# CH32F207VCT6-R1.net
KiCad netlist of a schematic drawn in Altium Designer
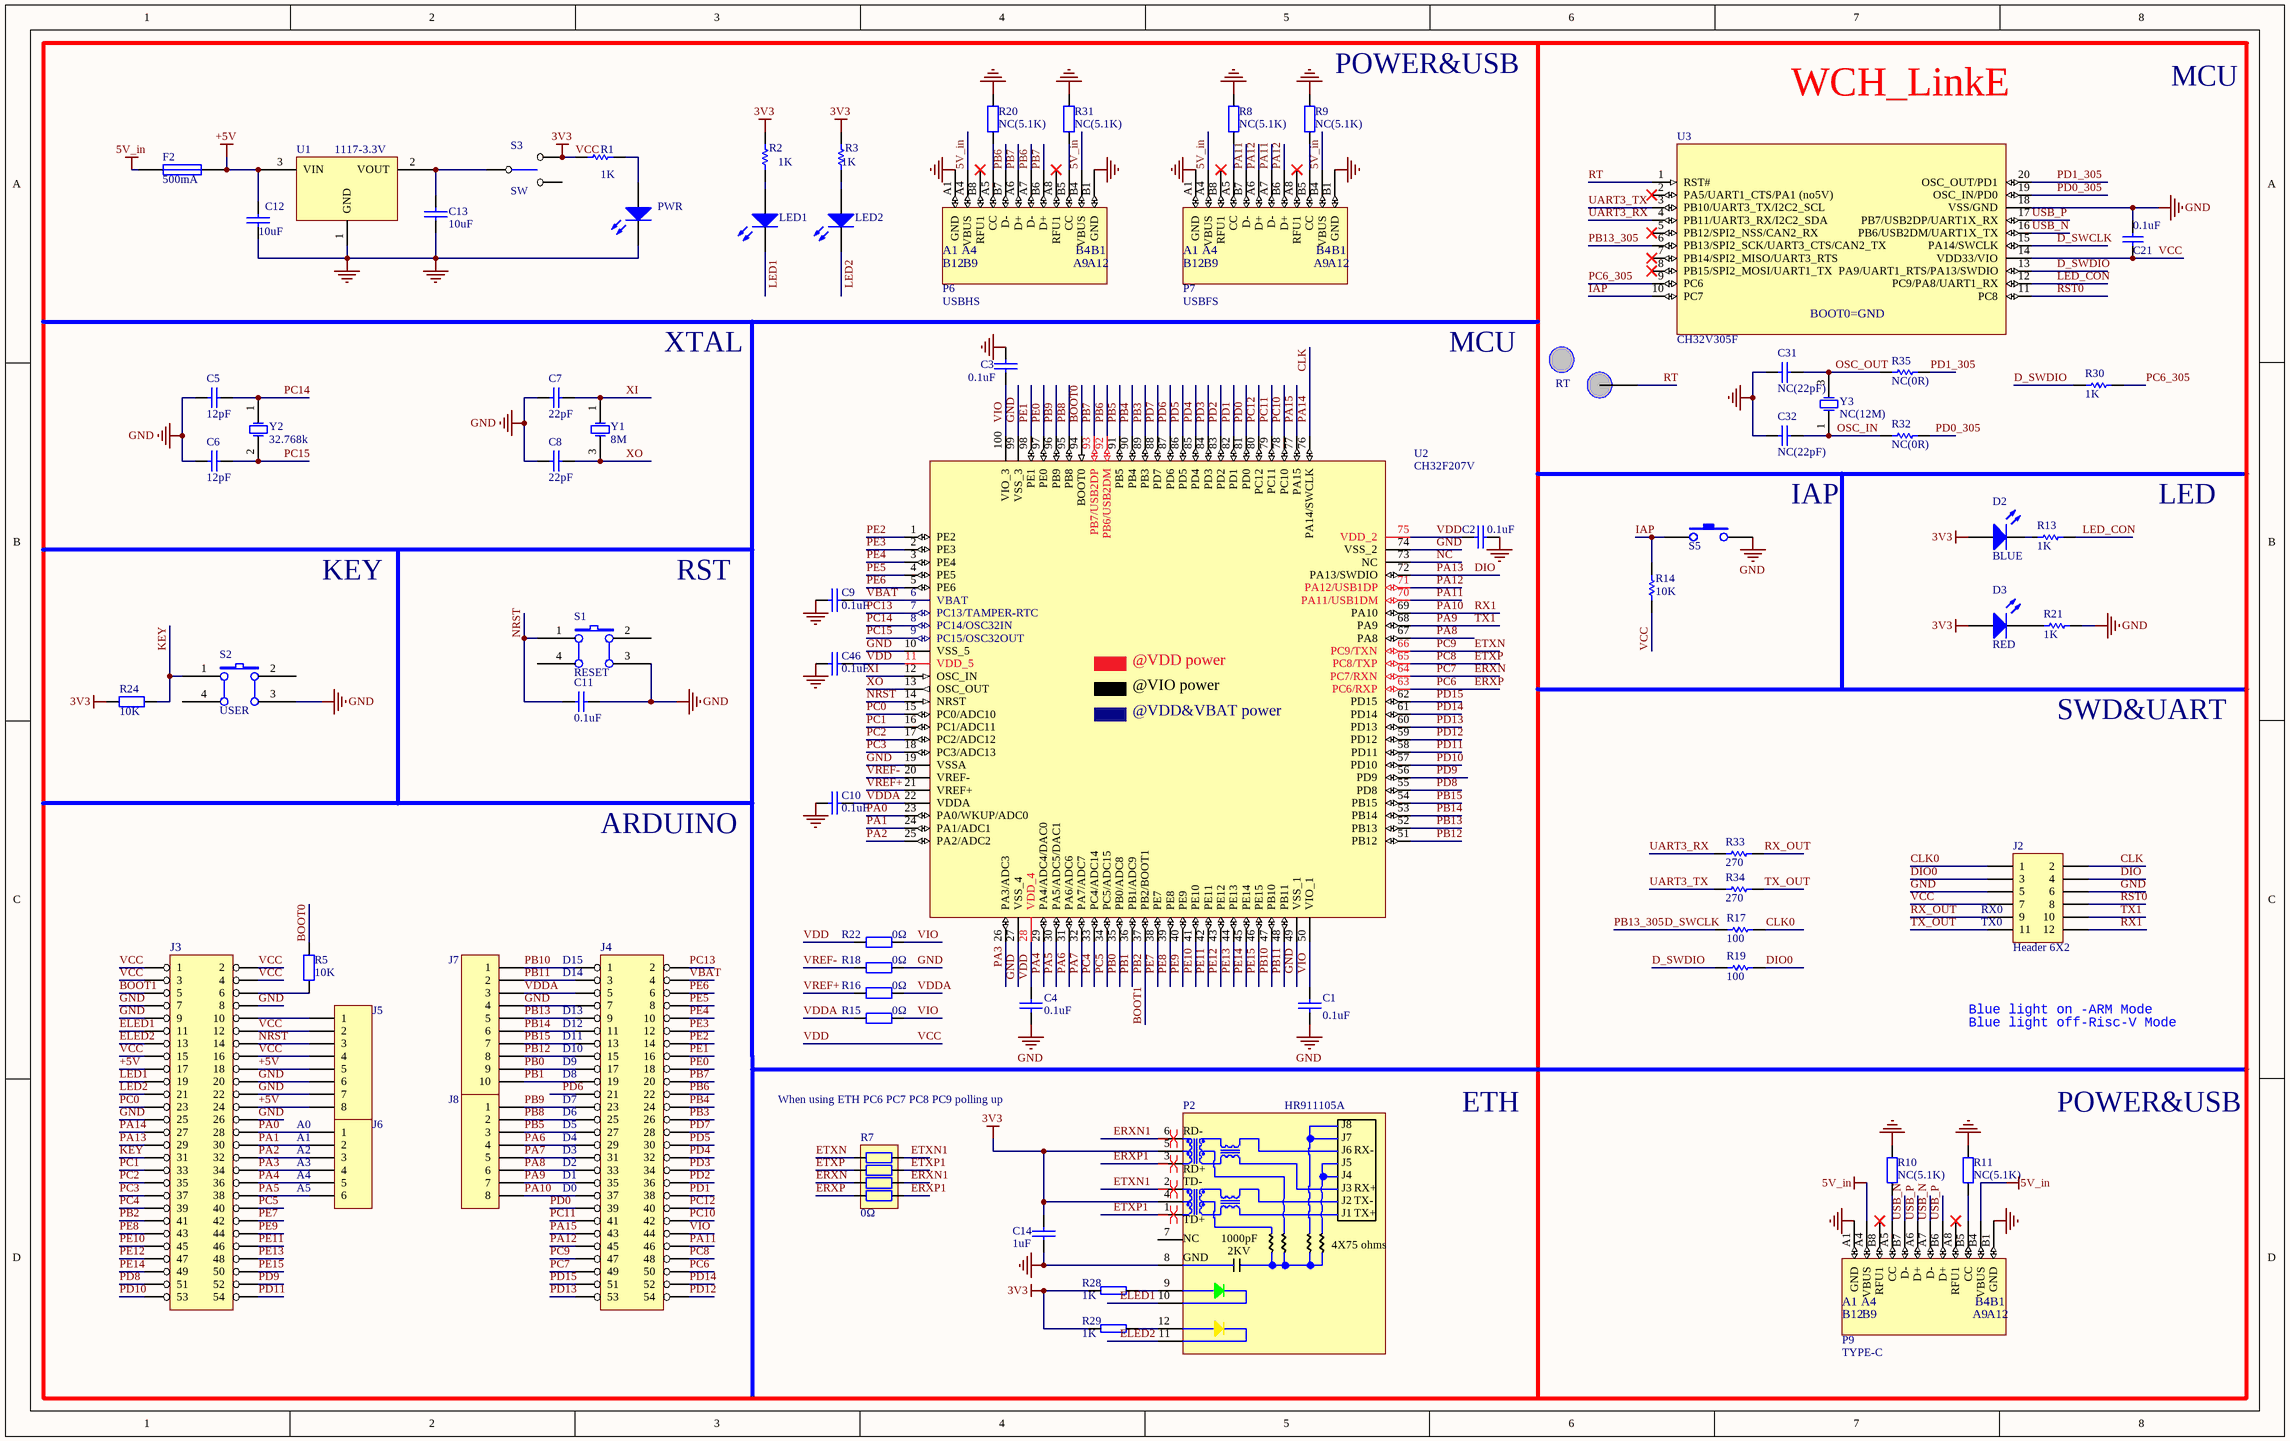
[diagram p0: CH32F207VCT6-R1.SchDoc]

(export (version "E")
  (design (tool "Eeschema 10.0.6"))
  (components
    (comp (ref "C1")
      (value "0.1uF")
      (footprint "0603_C")
      (description "Capacitor")
      (libsource (lib "*") (part "CAP"))
    )
    (comp (ref "C2")
      (value "0.1uF")
      (footprint "0603_C")
      (description "Capacitor")
      (libsource (lib "*") (part "CAP"))
    )
    (comp (ref "C3")
      (value "0.1uF")
      (footprint "0603_C")
      (description "Capacitor")
      (libsource (lib "*") (part "CAP"))
    )
    (comp (ref "C4")
      (value "0.1uF")
      (footprint "0603_C")
      (description "Capacitor")
      (libsource (lib "*") (part "CAP"))
    )
    (comp (ref "C5")
      (value "12pF")
      (footprint "0603_C")
      (description "Capacitor")
      (libsource (lib "Miscellaneous Devices") (part "Cap"))
    )
    (comp (ref "C6")
      (value "12pF")
      (footprint "0603_C")
      (description "Capacitor")
      (libsource (lib "Miscellaneous Devices") (part "Cap"))
    )
    (comp (ref "C7")
      (value "22pF")
      (footprint "0603_C")
      (description "Capacitor")
      (libsource (lib "Miscellaneous Devices") (part "Cap"))
    )
    (comp (ref "C8")
      (value "22pF")
      (footprint "0603_C")
      (description "Capacitor")
      (libsource (lib "Miscellaneous Devices") (part "Cap"))
    )
    (comp (ref "C9")
      (value "0.1uF")
      (footprint "0603_C")
      (description "Capacitor")
      (libsource (lib "*") (part "CAP"))
    )
    (comp (ref "C10")
      (value "0.1uF")
      (footprint "0603_C")
      (description "Capacitor")
      (libsource (lib "*") (part "CAP"))
    )
    (comp (ref "C11")
      (value "0.1uF")
      (footprint "0603_C")
      (description "Capacitor")
      (libsource (lib "Miscellaneous Devices") (part "Cap"))
    )
    (comp (ref "C12")
      (value "10uF")
      (footprint "3216_C")
      (description "Capacitor")
      (libsource (lib "*") (part "CAP"))
    )
    (comp (ref "C13")
      (value "10uF")
      (footprint "3216_C")
      (description "Capacitor")
      (libsource (lib "*") (part "CAP"))
    )
    (comp (ref "C14")
      (value "1uF")
      (footprint "0603_C")
      (description "Capacitor")
      (libsource (lib "*") (part "CAP"))
    )
    (comp (ref "C21")
      (value "0.1uF")
      (footprint "0603_C")
      (description "Capacitor")
      (libsource (lib "Miscellaneous Devices") (part "Cap"))
    )
    (comp (ref "C31")
      (value "NC(22pF)")
      (footprint "0603_C")
      (description "Capacitor")
      (libsource (lib "*") (part "Cap"))
    )
    (comp (ref "C32")
      (value "NC(22pF)")
      (footprint "0603_C")
      (description "Capacitor")
      (libsource (lib "*") (part "Cap"))
    )
    (comp (ref "C46")
      (value "0.1uF")
      (footprint "0603_C")
      (description "Capacitor")
      (libsource (lib "*") (part "CAP"))
    )
    (comp (ref "D2")
      (value "BLUE")
      (footprint "0603+")
      (description "Typical RED, GREEN, YELLOW, AMBER GaAs LED")
      (libsource (lib "MYLIB") (part "D0603"))
    )
    (comp (ref "D3")
      (value "RED")
      (footprint "0603+")
      (description "Typical RED, GREEN, YELLOW, AMBER GaAs LED")
      (libsource (lib "MYLIB") (part "D0603"))
    )
    (comp (ref "F2")
      (value "500mA")
      (footprint "0805")
      (description "Fuse")
      (libsource (lib "*") (part "FUSE1"))
    )
    (comp (ref "J2")
      (value "Header 6X2")
      (footprint "IDC12-2.54mm")
      (description "Header, 6-Pin, Dual row")
      (libsource (lib "Miscellaneous Connectors") (part "Header 6X2"))
    )
    (comp (ref "J3")
      (value "HEADER 27x2")
      (footprint "MYPCB:IDC54-2.54MM")
      (description "Header, 27-Pin, Dual row")
      (libsource (lib "wch_sch_others") (part "HEADER 27x2"))
    )
    (comp (ref "J4")
      (value "HEADER 27x2")
      (footprint "MYPCB:IDC54-2.54MM")
      (description "Header, 27-Pin, Dual row")
      (libsource (lib "wch_sch_others") (part "HEADER 27x2"))
    )
    (comp (ref "J5")
      (value "Header 8")
      (footprint "SIP8-2.54mm")
      (description "Header, 8-Pin")
      (libsource (lib "Miscellaneous Connectors") (part "Header 8"))
    )
    (comp (ref "J6")
      (value "Header 6")
      (footprint "SIP6-2.54MM")
      (description "Header, 6-Pin")
      (libsource (lib "Miscellaneous Connectors") (part "Header 6"))
    )
    (comp (ref "J7")
      (value "Header 10")
      (footprint "SIP10-2.54mm")
      (description "Header, 10-Pin")
      (libsource (lib "Miscellaneous Connectors") (part "Header 10"))
    )
    (comp (ref "J8")
      (value "Header 8")
      (footprint "SIP8-2.54mm")
      (description "Header, 8-Pin")
      (libsource (lib "") (part "Header 8_1"))
    )
    (comp (ref "LED1")
      (value "LED1   blue")
      (footprint "0603+")
      (description "Typical INFRARED GaAs LED")
      (libsource (lib "Miscellaneous Devices") (part "LED0"))
    )
    (comp (ref "LED2")
      (value "LED2  blue")
      (footprint "0603+")
      (description "Typical INFRARED GaAs LED")
      (libsource (lib "Miscellaneous Devices") (part "LED0"))
    )
    (comp (ref "P2") (value "HR911105A") (footprint "HR911105A") (libsource (lib "*") (part "HR911105A")))
    (comp (ref "P6")
      (value "USBHS")
      (footprint "TYPE-C-Receptacle-2.0")
      (libsource (lib "*") (part "TYPE-C1"))
    )
    (comp (ref "P7")
      (value "USBFS")
      (footprint "TYPE-C-Receptacle-2.0")
      (libsource (lib "*") (part "TYPE-C1"))
    )
    (comp (ref "P9")
      (value "TYPE-C")
      (footprint "TYPE-C-Receptacle-2.0")
      (libsource (lib "*") (part "TYPE-C1"))
    )
    (comp (ref "PWR")
      (value "POWER  red")
      (footprint "0603+")
      (description "Typical INFRARED GaAs LED")
      (libsource (lib "Miscellaneous Devices") (part "LED0"))
    )
    (comp (ref "R1")
      (value "1K")
      (footprint "0603")
      (description "Semiconductor Resistor")
      (libsource (lib "Miscellaneous Devices") (part "Res Semi"))
    )
    (comp (ref "R2")
      (value "1K")
      (footprint "0603")
      (description "Semiconductor Resistor")
      (libsource (lib "Miscellaneous Devices") (part "Res Semi"))
    )
    (comp (ref "R3")
      (value "1K")
      (footprint "0603")
      (description "Semiconductor Resistor")
      (libsource (lib "Miscellaneous Devices") (part "Res Semi"))
    )
    (comp (ref "R5")
      (value "10K")
      (footprint "0603")
      (description "Resistor")
      (libsource (lib "") (part "Res2_1"))
    )
    (comp (ref "R7")
      (value "0Ω")
      (footprint "RCA-8P4R-0603")
      (description "贴片网络排阻")
      (libsource (lib "wch_sch_others") (part "R-8P4R"))
    )
    (comp (ref "R8")
      (value "NC(5.1K)")
      (footprint "0603")
      (description "Resistor")
      (libsource (lib "") (part "Res2_2"))
    )
    (comp (ref "R9")
      (value "NC(5.1K)")
      (footprint "0603")
      (description "Resistor")
      (libsource (lib "") (part "Res2_2"))
    )
    (comp (ref "R10")
      (value "NC(5.1K)")
      (footprint "0603")
      (description "Resistor")
      (libsource (lib "") (part "Res2_1"))
    )
    (comp (ref "R11")
      (value "NC(5.1K)")
      (footprint "0603")
      (description "Resistor")
      (libsource (lib "") (part "Res2_1"))
    )
    (comp (ref "R13")
      (value "1K")
      (footprint "0603")
      (description "Resistor")
      (libsource (lib "MYLIB") (part "0603-1"))
    )
    (comp (ref "R14")
      (value "10K")
      (footprint "0603")
      (description "Resistor")
      (libsource (lib "MYLIB") (part "0603-1"))
    )
    (comp (ref "R15")
      (value "0Ω")
      (footprint "0603")
      (description "Resistor")
      (libsource (lib "Miscellaneous Devices") (part "Res2"))
    )
    (comp (ref "R16")
      (value "0Ω")
      (footprint "0603")
      (description "Resistor")
      (libsource (lib "Miscellaneous Devices") (part "Res2"))
    )
    (comp (ref "R17")
      (value "100")
      (footprint "0603")
      (description "Resistor")
      (libsource (lib "MYLIB") (part "0603-1"))
    )
    (comp (ref "R18")
      (value "0Ω")
      (footprint "0603")
      (description "Resistor")
      (libsource (lib "Miscellaneous Devices") (part "Res2"))
    )
    (comp (ref "R19")
      (value "100")
      (footprint "0603")
      (description "Resistor")
      (libsource (lib "MYLIB") (part "0603-1"))
    )
    (comp (ref "R20")
      (value "NC(5.1K)")
      (footprint "0603")
      (description "Resistor")
      (libsource (lib "") (part "Res2_2"))
    )
    (comp (ref "R21")
      (value "1K")
      (footprint "0603")
      (description "Resistor")
      (libsource (lib "MYLIB") (part "0603-1"))
    )
    (comp (ref "R22")
      (value "0Ω")
      (footprint "0603")
      (description "Resistor")
      (libsource (lib "Miscellaneous Devices") (part "Res2"))
    )
    (comp (ref "R24")
      (value "10K")
      (footprint "0603")
      (description "Resistor")
      (libsource (lib "Miscellaneous Devices") (part "Res2"))
    )
    (comp (ref "R28") (value "1K") (footprint "0603") (libsource (lib "wch_sch_others") (part "RES")))
    (comp (ref "R29") (value "1K") (footprint "0603") (libsource (lib "wch_sch_others") (part "RES")))
    (comp (ref "R30")
      (value "1K")
      (footprint "0603")
      (description "Resistor")
      (libsource (lib "MYLIB") (part "0603-1"))
    )
    (comp (ref "R31")
      (value "NC(5.1K)")
      (footprint "0603")
      (description "Resistor")
      (libsource (lib "") (part "Res2_2"))
    )
    (comp (ref "R32")
      (value "NC(0R)")
      (footprint "0603")
      (description "Resistor")
      (libsource (lib "MYLIB") (part "0603-1"))
    )
    (comp (ref "R33")
      (value "270")
      (footprint "0603")
      (description "Resistor")
      (libsource (lib "MYLIB") (part "0603-1"))
    )
    (comp (ref "R34")
      (value "270")
      (footprint "0603")
      (description "Resistor")
      (libsource (lib "MYLIB") (part "0603-1"))
    )
    (comp (ref "R35")
      (value "NC(0R)")
      (footprint "0603")
      (description "Resistor")
      (libsource (lib "MYLIB") (part "0603-1"))
    )
    (comp (ref "RT")
      (value "Testpoint")
      (footprint "TESTPOINT1")
      (description "测试点")
      (libsource (lib "wch_sch_others") (part "Testpoint"))
    )
    (comp (ref "S1")
      (value "RESET")
      (footprint "KEYX")
      (description "SE PUSHBUTTON")
      (libsource (lib "Documents") (part "SW PUSHBUTTON"))
    )
    (comp (ref "S2")
      (value "USER")
      (footprint "KEYX")
      (description "SE PUSHBUTTON")
      (libsource (lib "Documents") (part "SW PUSHBUTTON"))
    )
    (comp (ref "S3") (value "SW") (footprint "SW1") (libsource (lib "MYSCH") (part "SW")))
    (comp (ref "S5") (value "KEY") (footprint "贴片按键") (libsource (lib "*") (part "KEY")))
    (comp (ref "U1")
      (value "1117-3.3V")
      (footprint "SOT-223")
      (libsource (lib "wch_sch_others") (part "1117-3.3V"))
    )
    (comp (ref "U2")
      (value "CH32F207V")
      (footprint "LQFP100")
      (description "ARM M3 HD-MCU, 144MHz, USB_480M, USB OTG, 1000M Ethernet MAC, 2*CAN")
      (libsource (lib "CHXXX") (part "CH32F207V"))
    )
    (comp (ref "U3")
      (value "CH32V305F")
      (footprint "TSSOP20")
      (description "RISC-V FPU HD-MCU, 144MHz, USB_480M, CAN, UART*2, SPI")
      (libsource (lib "CHXXX") (part "CH32V305F"))
    )
    (comp (ref "Y1")
      (value "8M")
      (footprint "XT3225")
      (description "Crystal Oscillator")
      (libsource (lib "Miscellaneous Devices") (part "XTAL"))
    )
    (comp (ref "Y2")
      (value "32.768k")
      (footprint "FC-135")
      (description "Crystal Oscillator")
      (libsource (lib "") (part "XTAL_1"))
    )
    (comp (ref "Y3")
      (value "NC(12M)")
      (footprint "XT3225")
      (description "Crystal Oscillator")
      (libsource (lib "*") (part "XTAL"))
    )
  )
  (nets
    (net (code "1") (name "+5V") (class "Default")
      (node (ref "C12") (pin "1") (pinfunction "1_1") (pintype "passive"))
      (node (ref "F2") (pin "2") (pinfunction "2_2") (pintype "passive"))
      (node (ref "J3") (pin "17") (pinfunction "17_17") (pintype "passive"))
      (node (ref "J3") (pin "18") (pinfunction "18_18") (pintype "passive"))
      (node (ref "J3") (pin "24") (pinfunction "24_24") (pintype "passive"))
      (node (ref "J5") (pin "5") (pinfunction "5_5") (pintype "passive"))
      (node (ref "J5") (pin "8") (pinfunction "8_8") (pintype "passive"))
      (node (ref "U1") (pin "3") (pinfunction "VIN_3") (pintype "passive"))
    )
    (net (code "2") (name "/BOOT0") (class "Default")
      (node (ref "R5") (pin "2") (pinfunction "2_2") (pintype "passive"))
      (node (ref "U2") (pin "94") (pinfunction "BOOT0_94") (pintype "input"))
    )
    (net (code "3") (name "/BOOT1") (class "Default")
      (node (ref "J3") (pin "41") (pinfunction "41_41") (pintype "passive"))
      (node (ref "J3") (pin "5") (pinfunction "5_5") (pintype "passive"))
      (node (ref "U2") (pin "37") (pinfunction "PB2/BOOT1_37") (pintype "bidirectional"))
    )
    (net (code "4") (name "/CLK") (class "Default")
      (node (ref "J2") (pin "2") (pinfunction "2_2") (pintype "passive"))
      (node (ref "J3") (pin "27") (pinfunction "27_27") (pintype "passive"))
      (node (ref "U2") (pin "76") (pinfunction "PA14/SWCLK_76") (pintype "bidirectional"))
    )
    (net (code "5") (name "/CLK0") (class "Default")
      (node (ref "J2") (pin "1") (pinfunction "1_1") (pintype "passive"))
      (node (ref "R17") (pin "1") (pinfunction "1_1") (pintype "passive"))
    )
    (net (code "6") (name "/DIO") (class "Default")
      (node (ref "J2") (pin "4") (pinfunction "4_4") (pintype "passive"))
      (node (ref "J3") (pin "29") (pinfunction "29_29") (pintype "passive"))
      (node (ref "U2") (pin "72") (pinfunction "PA13/SWDIO_72") (pintype "bidirectional"))
    )
    (net (code "7") (name "/DIO0") (class "Default")
      (node (ref "J2") (pin "3") (pinfunction "3_3") (pintype "passive"))
      (node (ref "R19") (pin "1") (pinfunction "1_1") (pintype "passive"))
    )
    (net (code "8") (name "/D_SWCLK") (class "Default")
      (node (ref "R17") (pin "2") (pinfunction "2_2") (pintype "passive"))
      (node (ref "U3") (pin "15") (pinfunction "PA14/SWCLK_15") (pintype "bidirectional"))
      (node (ref "U3") (pin "6") (pinfunction "PB13/SPI2_SCK/UART3_CTS/CAN2_TX_6") (pintype "bidirectional"))
    )
    (net (code "9") (name "/D_SWDIO") (class "Default")
      (node (ref "R19") (pin "2") (pinfunction "2_2") (pintype "passive"))
      (node (ref "R30") (pin "1") (pinfunction "1_1") (pintype "passive"))
      (node (ref "U3") (pin "13") (pinfunction "PA9/UART1_RTS/PA13/SWDIO_13") (pintype "bidirectional"))
    )
    (net (code "10") (name "/ELED1") (class "Default")
      (node (ref "J3") (pin "11") (pinfunction "11_11") (pintype "passive"))
      (node (ref "P2") (pin "10") (pintype "passive"))
    )
    (net (code "11") (name "/ELED2") (class "Default")
      (node (ref "J3") (pin "13") (pinfunction "13_13") (pintype "passive"))
      (node (ref "P2") (pin "11") (pintype "passive"))
    )
    (net (code "12") (name "/ERXN") (class "Default")
      (node (ref "J4") (pin "49") (pinfunction "49_49") (pintype "passive"))
      (node (ref "R7") (pin "3") (pinfunction "3_3") (pintype "passive"))
      (node (ref "U2") (pin "64") (pinfunction "PC7/RXN_64") (pintype "bidirectional"))
    )
    (net (code "13") (name "/ERXN1") (class "Default")
      (node (ref "P2") (pin "6") (pintype "passive"))
      (node (ref "R7") (pin "6") (pinfunction "6_6") (pintype "passive"))
    )
    (net (code "14") (name "/ERXP") (class "Default")
      (node (ref "J4") (pin "50") (pinfunction "50_50") (pintype "passive"))
      (node (ref "R7") (pin "4") (pinfunction "4_4") (pintype "passive"))
      (node (ref "U2") (pin "63") (pinfunction "PC6/RXP_63") (pintype "bidirectional"))
    )
    (net (code "15") (name "/ERXP1") (class "Default")
      (node (ref "P2") (pin "3") (pintype "passive"))
      (node (ref "R7") (pin "5") (pinfunction "5_5") (pintype "passive"))
    )
    (net (code "16") (name "/ETXN") (class "Default")
      (node (ref "J4") (pin "47") (pinfunction "47_47") (pintype "passive"))
      (node (ref "R7") (pin "1") (pinfunction "1_1") (pintype "passive"))
      (node (ref "U2") (pin "66") (pinfunction "PC9/TXN_66") (pintype "bidirectional"))
    )
    (net (code "17") (name "/ETXN1") (class "Default")
      (node (ref "P2") (pin "2") (pintype "passive"))
      (node (ref "R7") (pin "8") (pinfunction "8_8") (pintype "passive"))
    )
    (net (code "18") (name "/ETXP") (class "Default")
      (node (ref "J4") (pin "48") (pinfunction "48_48") (pintype "passive"))
      (node (ref "R7") (pin "2") (pinfunction "2_2") (pintype "passive"))
      (node (ref "U2") (pin "65") (pinfunction "PC8/TXP_65") (pintype "bidirectional"))
    )
    (net (code "19") (name "/ETXP1") (class "Default")
      (node (ref "P2") (pin "1") (pintype "passive"))
      (node (ref "R7") (pin "7") (pinfunction "7_7") (pintype "passive"))
    )
    (net (code "20") (name "/IAP") (class "Default")
      (node (ref "R14") (pin "1") (pinfunction "1_1") (pintype "passive"))
      (node (ref "S5") (pin "1") (pinfunction "1_1") (pintype "passive"))
      (node (ref "U3") (pin "10") (pinfunction "PC7_10") (pintype "bidirectional"))
    )
    (net (code "21") (name "/KEY") (class "Default")
      (node (ref "J3") (pin "31") (pinfunction "31_31") (pintype "passive"))
      (node (ref "R24") (pin "1") (pinfunction "1_1") (pintype "passive"))
      (node (ref "S2") (pin "1") (pinfunction "A0_1") (pintype "passive"))
    )
    (net (code "22") (name "/LED1") (class "Default")
      (node (ref "J3") (pin "19") (pinfunction "19_19") (pintype "passive"))
      (node (ref "LED1") (pin "2") (pinfunction "K_2") (pintype "passive"))
    )
    (net (code "23") (name "/LED2") (class "Default")
      (node (ref "J3") (pin "21") (pinfunction "21_21") (pintype "passive"))
      (node (ref "LED2") (pin "2") (pinfunction "K_2") (pintype "passive"))
    )
    (net (code "24") (name "/LED_CON") (class "Default")
      (node (ref "R13") (pin "1") (pinfunction "1_1") (pintype "passive"))
      (node (ref "U3") (pin "12") (pinfunction "PC9/PA8/UART1_RX_12") (pintype "bidirectional"))
    )
    (net (code "25") (name "/NC") (class "Default")
      (node (ref "U2") (pin "73") (pinfunction "NC_73") (pintype "tri_state"))
    )
    (net (code "26") (name "/NRST") (class "Default")
      (node (ref "C11") (pin "2") (pinfunction "2_2") (pintype "passive"))
      (node (ref "J3") (pin "14") (pinfunction "14_14") (pintype "passive"))
      (node (ref "J5") (pin "3") (pinfunction "3_3") (pintype "passive"))
      (node (ref "S1") (pin "1") (pinfunction "A0_1") (pintype "passive"))
      (node (ref "U2") (pin "14") (pinfunction "NRST_14") (pintype "input"))
    )
    (net (code "27") (name "/OSC_IN") (class "Default")
      (node (ref "C32") (pin "2") (pinfunction "2_2") (pintype "passive"))
      (node (ref "R32") (pin "2") (pinfunction "2_2") (pintype "passive"))
      (node (ref "Y3") (pin "1") (pinfunction "OSC1_1") (pintype "passive"))
    )
    (net (code "28") (name "/OSC_OUT") (class "Default")
      (node (ref "C31") (pin "2") (pinfunction "2_2") (pintype "passive"))
      (node (ref "R35") (pin "2") (pinfunction "2_2") (pintype "passive"))
      (node (ref "Y3") (pin "3") (pinfunction "OSC2_3") (pintype "passive"))
    )
    (net (code "29") (name "/PA0") (class "Default")
      (node (ref "J3") (pin "28") (pinfunction "28_28") (pintype "passive"))
      (node (ref "J6") (pin "1") (pinfunction "1_1") (pintype "passive"))
      (node (ref "U2") (pin "23") (pinfunction "PA0/WKUP/ADC0_23") (pintype "bidirectional"))
    )
    (net (code "30") (name "/PA1") (class "Default")
      (node (ref "J3") (pin "30") (pinfunction "30_30") (pintype "passive"))
      (node (ref "J6") (pin "2") (pinfunction "2_2") (pintype "passive"))
      (node (ref "U2") (pin "24") (pinfunction "PA1/ADC1_24") (pintype "bidirectional"))
    )
    (net (code "31") (name "/PA2") (class "Default")
      (node (ref "J3") (pin "32") (pinfunction "32_32") (pintype "passive"))
      (node (ref "J6") (pin "3") (pinfunction "3_3") (pintype "passive"))
      (node (ref "U2") (pin "25") (pinfunction "PA2/ADC2_25") (pintype "bidirectional"))
    )
    (net (code "32") (name "/PA3") (class "Default")
      (node (ref "J3") (pin "34") (pinfunction "34_34") (pintype "passive"))
      (node (ref "J6") (pin "4") (pinfunction "4_4") (pintype "passive"))
      (node (ref "U2") (pin "26") (pinfunction "PA3/ADC3_26") (pintype "bidirectional"))
    )
    (net (code "33") (name "/PA4") (class "Default")
      (node (ref "J3") (pin "36") (pinfunction "36_36") (pintype "passive"))
      (node (ref "J6") (pin "5") (pinfunction "5_5") (pintype "passive"))
      (node (ref "U2") (pin "29") (pinfunction "PA4/ADC4/DAC0_29") (pintype "bidirectional"))
    )
    (net (code "34") (name "/PA5") (class "Default")
      (node (ref "J3") (pin "38") (pinfunction "38_38") (pintype "passive"))
      (node (ref "J6") (pin "6") (pinfunction "6_6") (pintype "passive"))
      (node (ref "U2") (pin "30") (pinfunction "PA5/ADC5/DAC1_30") (pintype "bidirectional"))
    )
    (net (code "35") (name "/PA6") (class "Default")
      (node (ref "J4") (pin "29") (pinfunction "29_29") (pintype "passive"))
      (node (ref "J8") (pin "4") (pinfunction "4_4") (pintype "passive"))
      (node (ref "U2") (pin "31") (pinfunction "PA6/ADC6_31") (pintype "bidirectional"))
    )
    (net (code "36") (name "/PA7") (class "Default")
      (node (ref "J4") (pin "31") (pinfunction "31_31") (pintype "passive"))
      (node (ref "J8") (pin "5") (pinfunction "5_5") (pintype "passive"))
      (node (ref "U2") (pin "32") (pinfunction "PA7/ADC7_32") (pintype "bidirectional"))
    )
    (net (code "37") (name "/PA8") (class "Default")
      (node (ref "J4") (pin "33") (pinfunction "33_33") (pintype "passive"))
      (node (ref "J8") (pin "6") (pinfunction "6_6") (pintype "passive"))
      (node (ref "U2") (pin "67") (pinfunction "PA8_67") (pintype "bidirectional"))
    )
    (net (code "38") (name "/PA9") (class "Default")
      (node (ref "J2") (pin "10") (pinfunction "10_10") (pintype "passive"))
      (node (ref "J4") (pin "35") (pinfunction "35_35") (pintype "passive"))
      (node (ref "J8") (pin "7") (pinfunction "7_7") (pintype "passive"))
      (node (ref "U2") (pin "68") (pinfunction "PA9_68") (pintype "bidirectional"))
    )
    (net (code "39") (name "/PA10") (class "Default")
      (node (ref "J2") (pin "12") (pinfunction "12_12") (pintype "passive"))
      (node (ref "J4") (pin "37") (pinfunction "37_37") (pintype "passive"))
      (node (ref "J8") (pin "8") (pinfunction "8_8") (pintype "passive"))
      (node (ref "U2") (pin "69") (pinfunction "PA10_69") (pintype "bidirectional"))
    )
    (net (code "40") (name "/PA11") (class "Default")
      (node (ref "J4") (pin "46") (pinfunction "46_46") (pintype "passive"))
      (node (ref "P7") (pin "A7") (pinfunction "D-_A7") (pintype "bidirectional"))
      (node (ref "P7") (pin "B7") (pinfunction "D-_B7") (pintype "bidirectional"))
      (node (ref "U2") (pin "70") (pinfunction "PA11/USB1DM_70") (pintype "bidirectional"))
    )
    (net (code "41") (name "/PA12") (class "Default")
      (node (ref "J4") (pin "45") (pinfunction "45_45") (pintype "passive"))
      (node (ref "P7") (pin "A6") (pinfunction "D+_A6") (pintype "bidirectional"))
      (node (ref "P7") (pin "B6") (pinfunction "D+_B6") (pintype "bidirectional"))
      (node (ref "U2") (pin "71") (pinfunction "PA12/USB1DP_71") (pintype "bidirectional"))
    )
    (net (code "42") (name "/PA15") (class "Default")
      (node (ref "J4") (pin "43") (pinfunction "43_43") (pintype "passive"))
      (node (ref "U2") (pin "77") (pinfunction "PA15_77") (pintype "bidirectional"))
    )
    (net (code "43") (name "/PB0") (class "Default")
      (node (ref "J4") (pin "17") (pinfunction "17_17") (pintype "passive"))
      (node (ref "J7") (pin "9") (pinfunction "9_9") (pintype "passive"))
      (node (ref "U2") (pin "35") (pinfunction "PB0/ADC8_35") (pintype "bidirectional"))
    )
    (net (code "44") (name "/PB1") (class "Default")
      (node (ref "J4") (pin "19") (pinfunction "19_19") (pintype "passive"))
      (node (ref "J7") (pin "10") (pinfunction "10_10") (pintype "passive"))
      (node (ref "U2") (pin "36") (pinfunction "PB1/ADC9_36") (pintype "bidirectional"))
    )
    (net (code "45") (name "/PB3") (class "Default")
      (node (ref "J4") (pin "26") (pinfunction "26_26") (pintype "passive"))
      (node (ref "U2") (pin "89") (pinfunction "PB3_89") (pintype "bidirectional"))
    )
    (net (code "46") (name "/PB4") (class "Default")
      (node (ref "J4") (pin "24") (pinfunction "24_24") (pintype "passive"))
      (node (ref "U2") (pin "90") (pinfunction "PB4_90") (pintype "bidirectional"))
    )
    (net (code "47") (name "/PB5") (class "Default")
      (node (ref "J4") (pin "27") (pinfunction "27_27") (pintype "passive"))
      (node (ref "J8") (pin "3") (pinfunction "3_3") (pintype "passive"))
      (node (ref "U2") (pin "91") (pinfunction "PB5_91") (pintype "bidirectional"))
    )
    (net (code "48") (name "/PB6") (class "Default")
      (node (ref "J4") (pin "22") (pinfunction "22_22") (pintype "passive"))
      (node (ref "P6") (pin "A7") (pinfunction "D-_A7") (pintype "bidirectional"))
      (node (ref "P6") (pin "B7") (pinfunction "D-_B7") (pintype "bidirectional"))
      (node (ref "U2") (pin "92") (pinfunction "PB6/USB2DM_92") (pintype "bidirectional"))
    )
    (net (code "49") (name "/PB7") (class "Default")
      (node (ref "J4") (pin "20") (pinfunction "20_20") (pintype "passive"))
      (node (ref "P6") (pin "A6") (pinfunction "D+_A6") (pintype "bidirectional"))
      (node (ref "P6") (pin "B6") (pinfunction "D+_B6") (pintype "bidirectional"))
      (node (ref "U2") (pin "93") (pinfunction "PB7/USB2DP_93") (pintype "bidirectional"))
    )
    (net (code "50") (name "/PB8") (class "Default")
      (node (ref "J4") (pin "25") (pinfunction "25_25") (pintype "passive"))
      (node (ref "J8") (pin "2") (pinfunction "2_2") (pintype "passive"))
      (node (ref "U2") (pin "95") (pinfunction "PB8_95") (pintype "bidirectional"))
    )
    (net (code "51") (name "/PB9") (class "Default")
      (node (ref "J4") (pin "23") (pinfunction "23_23") (pintype "passive"))
      (node (ref "J8") (pin "1") (pinfunction "1_1") (pintype "passive"))
      (node (ref "U2") (pin "96") (pinfunction "PB9_96") (pintype "bidirectional"))
    )
    (net (code "52") (name "/PB10") (class "Default")
      (node (ref "J4") (pin "1") (pinfunction "1_1") (pintype "passive"))
      (node (ref "J7") (pin "1") (pinfunction "1_1") (pintype "passive"))
      (node (ref "U2") (pin "47") (pinfunction "PB10_47") (pintype "bidirectional"))
    )
    (net (code "53") (name "/PB11") (class "Default")
      (node (ref "J4") (pin "3") (pinfunction "3_3") (pintype "passive"))
      (node (ref "J7") (pin "2") (pinfunction "2_2") (pintype "passive"))
      (node (ref "U2") (pin "48") (pinfunction "PB11_48") (pintype "bidirectional"))
    )
    (net (code "54") (name "/PB12") (class "Default")
      (node (ref "J4") (pin "15") (pinfunction "15_15") (pintype "passive"))
      (node (ref "J7") (pin "8") (pinfunction "8_8") (pintype "passive"))
      (node (ref "U2") (pin "51") (pinfunction "PB12_51") (pintype "bidirectional"))
    )
    (net (code "55") (name "/PB13") (class "Default")
      (node (ref "J4") (pin "9") (pinfunction "9_9") (pintype "passive"))
      (node (ref "J7") (pin "5") (pinfunction "5_5") (pintype "passive"))
      (node (ref "U2") (pin "52") (pinfunction "PB13_52") (pintype "bidirectional"))
    )
    (net (code "56") (name "/PB14") (class "Default")
      (node (ref "J4") (pin "11") (pinfunction "11_11") (pintype "passive"))
      (node (ref "J7") (pin "6") (pinfunction "6_6") (pintype "passive"))
      (node (ref "U2") (pin "53") (pinfunction "PB14_53") (pintype "bidirectional"))
    )
    (net (code "57") (name "/PB15") (class "Default")
      (node (ref "J4") (pin "13") (pinfunction "13_13") (pintype "passive"))
      (node (ref "J7") (pin "7") (pinfunction "7_7") (pintype "passive"))
      (node (ref "U2") (pin "54") (pinfunction "PB15_54") (pintype "bidirectional"))
    )
    (net (code "58") (name "/PC0") (class "Default")
      (node (ref "J3") (pin "23") (pinfunction "23_23") (pintype "passive"))
      (node (ref "U2") (pin "15") (pinfunction "PC0/ADC10_15") (pintype "bidirectional"))
    )
    (net (code "59") (name "/PC1") (class "Default")
      (node (ref "J3") (pin "33") (pinfunction "33_33") (pintype "passive"))
      (node (ref "U2") (pin "16") (pinfunction "PC1/ADC11_16") (pintype "bidirectional"))
    )
    (net (code "60") (name "/PC2") (class "Default")
      (node (ref "J3") (pin "35") (pinfunction "35_35") (pintype "passive"))
      (node (ref "U2") (pin "17") (pinfunction "PC2/ADC12_17") (pintype "bidirectional"))
    )
    (net (code "61") (name "/PC3") (class "Default")
      (node (ref "J3") (pin "37") (pinfunction "37_37") (pintype "passive"))
      (node (ref "U2") (pin "18") (pinfunction "PC3/ADC13_18") (pintype "bidirectional"))
    )
    (net (code "62") (name "/PC4") (class "Default")
      (node (ref "J3") (pin "39") (pinfunction "39_39") (pintype "passive"))
      (node (ref "U2") (pin "33") (pinfunction "PC4/ADC14_33") (pintype "bidirectional"))
    )
    (net (code "63") (name "/PC5") (class "Default")
      (node (ref "J3") (pin "40") (pinfunction "40_40") (pintype "passive"))
      (node (ref "U2") (pin "34") (pinfunction "PC5/ADC15_34") (pintype "bidirectional"))
    )
    (net (code "64") (name "/PC6_305") (class "Default")
      (node (ref "R30") (pin "2") (pinfunction "2_2") (pintype "passive"))
      (node (ref "U3") (pin "9") (pinfunction "PC6_9") (pintype "bidirectional"))
    )
    (net (code "65") (name "/PC10") (class "Default")
      (node (ref "J4") (pin "42") (pinfunction "42_42") (pintype "passive"))
      (node (ref "U2") (pin "78") (pinfunction "PC10_78") (pintype "bidirectional"))
    )
    (net (code "66") (name "/PC11") (class "Default")
      (node (ref "J4") (pin "41") (pinfunction "41_41") (pintype "passive"))
      (node (ref "U2") (pin "79") (pinfunction "PC11_79") (pintype "bidirectional"))
    )
    (net (code "67") (name "/PC12") (class "Default")
      (node (ref "J4") (pin "40") (pinfunction "40_40") (pintype "passive"))
      (node (ref "U2") (pin "80") (pinfunction "PC12_80") (pintype "bidirectional"))
    )
    (net (code "68") (name "/PC13") (class "Default")
      (node (ref "J4") (pin "2") (pinfunction "2_2") (pintype "passive"))
      (node (ref "U2") (pin "7") (pinfunction "PC13/TAMPER-RTC_7") (pintype "bidirectional"))
    )
    (net (code "69") (name "/PC14") (class "Default")
      (node (ref "C5") (pin "1") (pinfunction "1_1") (pintype "passive"))
      (node (ref "U2") (pin "8") (pinfunction "PC14/OSC32IN_8") (pintype "bidirectional"))
      (node (ref "Y2") (pin "1") (pinfunction "OSC1_1") (pintype "passive"))
    )
    (net (code "70") (name "/PC15") (class "Default")
      (node (ref "C6") (pin "1") (pinfunction "1_1") (pintype "passive"))
      (node (ref "U2") (pin "9") (pinfunction "PC15/OSC32OUT_9") (pintype "bidirectional"))
      (node (ref "Y2") (pin "2") (pinfunction "OSC2_2") (pintype "passive"))
    )
    (net (code "71") (name "/PD0") (class "Default")
      (node (ref "J4") (pin "39") (pinfunction "39_39") (pintype "passive"))
      (node (ref "U2") (pin "81") (pinfunction "PD0_81") (pintype "bidirectional"))
    )
    (net (code "72") (name "/PD0_305") (class "Default")
      (node (ref "R32") (pin "1") (pinfunction "1_1") (pintype "passive"))
      (node (ref "U3") (pin "19") (pinfunction "OSC_IN/PD0_19") (pintype "bidirectional"))
    )
    (net (code "73") (name "/PD1") (class "Default")
      (node (ref "J4") (pin "38") (pinfunction "38_38") (pintype "passive"))
      (node (ref "U2") (pin "82") (pinfunction "PD1_82") (pintype "bidirectional"))
    )
    (net (code "74") (name "/PD1_305") (class "Default")
      (node (ref "R35") (pin "1") (pinfunction "1_1") (pintype "passive"))
      (node (ref "U3") (pin "20") (pinfunction "OSC_OUT/PD1_20") (pintype "bidirectional"))
    )
    (net (code "75") (name "/PD2") (class "Default")
      (node (ref "J4") (pin "36") (pinfunction "36_36") (pintype "passive"))
      (node (ref "U2") (pin "83") (pinfunction "PD2_83") (pintype "bidirectional"))
    )
    (net (code "76") (name "/PD3") (class "Default")
      (node (ref "J4") (pin "34") (pinfunction "34_34") (pintype "passive"))
      (node (ref "U2") (pin "84") (pinfunction "PD3_84") (pintype "bidirectional"))
    )
    (net (code "77") (name "/PD4") (class "Default")
      (node (ref "J4") (pin "32") (pinfunction "32_32") (pintype "passive"))
      (node (ref "U2") (pin "85") (pinfunction "PD4_85") (pintype "bidirectional"))
    )
    (net (code "78") (name "/PD5") (class "Default")
      (node (ref "J4") (pin "30") (pinfunction "30_30") (pintype "passive"))
      (node (ref "U2") (pin "86") (pinfunction "PD5_86") (pintype "bidirectional"))
    )
    (net (code "79") (name "/PD6") (class "Default")
      (node (ref "J4") (pin "21") (pinfunction "21_21") (pintype "passive"))
      (node (ref "U2") (pin "87") (pinfunction "PD6_87") (pintype "bidirectional"))
    )
    (net (code "80") (name "/PD7") (class "Default")
      (node (ref "J4") (pin "28") (pinfunction "28_28") (pintype "passive"))
      (node (ref "U2") (pin "88") (pinfunction "PD7_88") (pintype "bidirectional"))
    )
    (net (code "81") (name "/PD8") (class "Default")
      (node (ref "J3") (pin "51") (pinfunction "51_51") (pintype "passive"))
      (node (ref "U2") (pin "55") (pinfunction "PD8_55") (pintype "bidirectional"))
    )
    (net (code "82") (name "/PD9") (class "Default")
      (node (ref "J3") (pin "52") (pinfunction "52_52") (pintype "passive"))
      (node (ref "U2") (pin "56") (pinfunction "PD9_56") (pintype "bidirectional"))
    )
    (net (code "83") (name "/PD10") (class "Default")
      (node (ref "J3") (pin "53") (pinfunction "53_53") (pintype "passive"))
      (node (ref "U2") (pin "57") (pinfunction "PD10_57") (pintype "bidirectional"))
    )
    (net (code "84") (name "/PD11") (class "Default")
      (node (ref "J3") (pin "54") (pinfunction "54_54") (pintype "passive"))
      (node (ref "U2") (pin "58") (pinfunction "PD11_58") (pintype "bidirectional"))
    )
    (net (code "85") (name "/PD12") (class "Default")
      (node (ref "J4") (pin "54") (pinfunction "54_54") (pintype "passive"))
      (node (ref "U2") (pin "59") (pinfunction "PD12_59") (pintype "bidirectional"))
    )
    (net (code "86") (name "/PD13") (class "Default")
      (node (ref "J4") (pin "53") (pinfunction "53_53") (pintype "passive"))
      (node (ref "U2") (pin "60") (pinfunction "PD13_60") (pintype "bidirectional"))
    )
    (net (code "87") (name "/PD14") (class "Default")
      (node (ref "J4") (pin "52") (pinfunction "52_52") (pintype "passive"))
      (node (ref "U2") (pin "61") (pinfunction "PD14_61") (pintype "bidirectional"))
    )
    (net (code "88") (name "/PD15") (class "Default")
      (node (ref "J4") (pin "51") (pinfunction "51_51") (pintype "passive"))
      (node (ref "U2") (pin "62") (pinfunction "PD15_62") (pintype "bidirectional"))
    )
    (net (code "89") (name "/PE0") (class "Default")
      (node (ref "J4") (pin "18") (pinfunction "18_18") (pintype "passive"))
      (node (ref "U2") (pin "97") (pinfunction "PE0_97") (pintype "bidirectional"))
    )
    (net (code "90") (name "/PE1") (class "Default")
      (node (ref "J4") (pin "16") (pinfunction "16_16") (pintype "passive"))
      (node (ref "U2") (pin "98") (pinfunction "PE1_98") (pintype "bidirectional"))
    )
    (net (code "91") (name "/PE2") (class "Default")
      (node (ref "J4") (pin "14") (pinfunction "14_14") (pintype "passive"))
      (node (ref "U2") (pin "1") (pinfunction "PE2_1") (pintype "bidirectional"))
    )
    (net (code "92") (name "/PE3") (class "Default")
      (node (ref "J4") (pin "12") (pinfunction "12_12") (pintype "passive"))
      (node (ref "U2") (pin "2") (pinfunction "PE3_2") (pintype "bidirectional"))
    )
    (net (code "93") (name "/PE4") (class "Default")
      (node (ref "J4") (pin "10") (pinfunction "10_10") (pintype "passive"))
      (node (ref "U2") (pin "3") (pinfunction "PE4_3") (pintype "bidirectional"))
    )
    (net (code "94") (name "/PE5") (class "Default")
      (node (ref "J4") (pin "8") (pinfunction "8_8") (pintype "passive"))
      (node (ref "U2") (pin "4") (pinfunction "PE5_4") (pintype "bidirectional"))
    )
    (net (code "95") (name "/PE6") (class "Default")
      (node (ref "J4") (pin "6") (pinfunction "6_6") (pintype "passive"))
      (node (ref "U2") (pin "5") (pinfunction "PE6_5") (pintype "bidirectional"))
    )
    (net (code "96") (name "/PE7") (class "Default")
      (node (ref "J3") (pin "42") (pinfunction "42_42") (pintype "passive"))
      (node (ref "U2") (pin "38") (pinfunction "PE7_38") (pintype "bidirectional"))
    )
    (net (code "97") (name "/PE8") (class "Default")
      (node (ref "J3") (pin "43") (pinfunction "43_43") (pintype "passive"))
      (node (ref "U2") (pin "39") (pinfunction "PE8_39") (pintype "bidirectional"))
    )
    (net (code "98") (name "/PE9") (class "Default")
      (node (ref "J3") (pin "44") (pinfunction "44_44") (pintype "passive"))
      (node (ref "U2") (pin "40") (pinfunction "PE9_40") (pintype "bidirectional"))
    )
    (net (code "99") (name "/PE10") (class "Default")
      (node (ref "J3") (pin "45") (pinfunction "45_45") (pintype "passive"))
      (node (ref "U2") (pin "41") (pinfunction "PE10_41") (pintype "bidirectional"))
    )
    (net (code "100") (name "/PE11") (class "Default")
      (node (ref "J3") (pin "46") (pinfunction "46_46") (pintype "passive"))
      (node (ref "U2") (pin "42") (pinfunction "PE11_42") (pintype "bidirectional"))
    )
    (net (code "101") (name "/PE12") (class "Default")
      (node (ref "J3") (pin "47") (pinfunction "47_47") (pintype "passive"))
      (node (ref "U2") (pin "43") (pinfunction "PE12_43") (pintype "bidirectional"))
    )
    (net (code "102") (name "/PE13") (class "Default")
      (node (ref "J3") (pin "48") (pinfunction "48_48") (pintype "passive"))
      (node (ref "U2") (pin "44") (pinfunction "PE13_44") (pintype "bidirectional"))
    )
    (net (code "103") (name "/PE14") (class "Default")
      (node (ref "J3") (pin "49") (pinfunction "49_49") (pintype "passive"))
      (node (ref "U2") (pin "45") (pinfunction "PE14_45") (pintype "bidirectional"))
    )
    (net (code "104") (name "/PE15") (class "Default")
      (node (ref "J3") (pin "50") (pinfunction "50_50") (pintype "passive"))
      (node (ref "U2") (pin "46") (pinfunction "PE15_46") (pintype "bidirectional"))
    )
    (net (code "105") (name "/RST0") (class "Default")
      (node (ref "J2") (pin "8") (pinfunction "8_8") (pintype "passive"))
      (node (ref "U3") (pin "11") (pinfunction "PC8_11") (pintype "bidirectional"))
    )
    (net (code "106") (name "/RT") (class "Default")
      (node (ref "RT") (pin "1") (pinfunction "point_1") (pintype "passive"))
      (node (ref "U3") (pin "1") (pinfunction "RST#_1") (pintype "input"))
    )
    (net (code "107") (name "/RX_OUT") (class "Default")
      (node (ref "J2") (pin "9") (pinfunction "9_9") (pintype "passive"))
      (node (ref "R33") (pin "1") (pinfunction "1_1") (pintype "passive"))
    )
    (net (code "108") (name "/TX_OUT") (class "Default")
      (node (ref "J2") (pin "11") (pinfunction "11_11") (pintype "passive"))
      (node (ref "R34") (pin "1") (pinfunction "1_1") (pintype "passive"))
    )
    (net (code "109") (name "/UART3_RX") (class "Default")
      (node (ref "R33") (pin "2") (pinfunction "2_2") (pintype "passive"))
      (node (ref "U3") (pin "4") (pinfunction "PB11/UART3_RX/I2C2_SDA_4") (pintype "bidirectional"))
    )
    (net (code "110") (name "/UART3_TX") (class "Default")
      (node (ref "R34") (pin "2") (pinfunction "2_2") (pintype "passive"))
      (node (ref "U3") (pin "3") (pinfunction "PB10/UART3_TX/I2C2_SCL_3") (pintype "bidirectional"))
    )
    (net (code "111") (name "/USB_N") (class "Default")
      (node (ref "P9") (pin "A7") (pinfunction "D-_A7") (pintype "bidirectional"))
      (node (ref "P9") (pin "B7") (pinfunction "D-_B7") (pintype "bidirectional"))
      (node (ref "U3") (pin "16") (pinfunction "PB6/USB2DM/UART1X_TX_16") (pintype "bidirectional"))
    )
    (net (code "112") (name "/USB_P") (class "Default")
      (node (ref "P9") (pin "A6") (pinfunction "D+_A6") (pintype "bidirectional"))
      (node (ref "P9") (pin "B6") (pinfunction "D+_B6") (pintype "bidirectional"))
      (node (ref "U3") (pin "17") (pinfunction "PB7/USB2DP/UART1X_RX_17") (pintype "bidirectional"))
    )
    (net (code "113") (name "/VBAT") (class "Default")
      (node (ref "C9") (pin "2") (pinfunction "2_2") (pintype "passive"))
      (node (ref "J4") (pin "4") (pinfunction "4_4") (pintype "passive"))
      (node (ref "U2") (pin "6") (pinfunction "VBAT_6") (pintype "power_in"))
    )
    (net (code "114") (name "/VDDA") (class "Default")
      (node (ref "C10") (pin "2") (pinfunction "2_2") (pintype "passive"))
      (node (ref "J4") (pin "5") (pinfunction "5_5") (pintype "passive"))
      (node (ref "J7") (pin "3") (pinfunction "3_3") (pintype "passive"))
      (node (ref "R15") (pin "2") (pinfunction "2_2") (pintype "passive"))
      (node (ref "R16") (pin "1") (pinfunction "1_1") (pintype "passive"))
      (node (ref "U2") (pin "22") (pinfunction "VDDA_22") (pintype "power_in"))
    )
    (net (code "115") (name "/VIO") (class "Default")
      (node (ref "C1") (pin "2") (pinfunction "2_2") (pintype "passive"))
      (node (ref "C3") (pin "1") (pinfunction "1_1") (pintype "passive"))
      (node (ref "J4") (pin "44") (pinfunction "44_44") (pintype "passive"))
      (node (ref "R15") (pin "1") (pinfunction "1_1") (pintype "passive"))
      (node (ref "R22") (pin "1") (pinfunction "1_1") (pintype "passive"))
      (node (ref "U2") (pin "100") (pinfunction "VIO_3_100") (pintype "power_in"))
      (node (ref "U2") (pin "50") (pinfunction "VIO_1_50") (pintype "power_in"))
    )
    (net (code "116") (name "/VREF+") (class "Default")
      (node (ref "R16") (pin "2") (pinfunction "2_2") (pintype "passive"))
      (node (ref "U2") (pin "21") (pinfunction "VREF+_21") (pintype "power_in"))
    )
    (net (code "117") (name "/VREF-") (class "Default")
      (node (ref "R18") (pin "2") (pinfunction "2_2") (pintype "passive"))
      (node (ref "U2") (pin "20") (pinfunction "VREF-_20") (pintype "power_in"))
    )
    (net (code "118") (name "/XI") (class "Default")
      (node (ref "C7") (pin "2") (pinfunction "2_2") (pintype "passive"))
      (node (ref "U2") (pin "12") (pinfunction "OSC_IN_12") (pintype "input"))
      (node (ref "Y1") (pin "1") (pinfunction "OSC1_1") (pintype "passive"))
    )
    (net (code "119") (name "/XO") (class "Default")
      (node (ref "C8") (pin "2") (pinfunction "2_2") (pintype "passive"))
      (node (ref "U2") (pin "13") (pinfunction "OSC_OUT_13") (pintype "output"))
      (node (ref "Y1") (pin "3") (pinfunction "OSC2_3") (pintype "passive"))
    )
    (net (code "120") (name "3V3") (class "Default")
      (node (ref "C14") (pin "2") (pinfunction "2_2") (pintype "passive"))
      (node (ref "C2") (pin "2") (pinfunction "2_2") (pintype "passive"))
      (node (ref "C21") (pin "1") (pinfunction "1_1") (pintype "passive"))
      (node (ref "C4") (pin "2") (pinfunction "2_2") (pintype "passive"))
      (node (ref "C46") (pin "1") (pinfunction "1_1") (pintype "passive"))
      (node (ref "D2") (pin "1") (pinfunction "A_1") (pintype "passive"))
      (node (ref "D3") (pin "1") (pinfunction "A_1") (pintype "passive"))
      (node (ref "J2") (pin "7") (pinfunction "7_7") (pintype "passive"))
      (node (ref "J3") (pin "1") (pinfunction "1_1") (pintype "passive"))
      (node (ref "J3") (pin "12") (pinfunction "12_12") (pintype "passive"))
      (node (ref "J3") (pin "15") (pinfunction "15_15") (pintype "passive"))
      (node (ref "J3") (pin "16") (pinfunction "16_16") (pintype "passive"))
      (node (ref "J3") (pin "2") (pinfunction "2_2") (pintype "passive"))
      (node (ref "J3") (pin "3") (pinfunction "3_3") (pintype "passive"))
      (node (ref "J3") (pin "4") (pinfunction "4_4") (pintype "passive"))
      (node (ref "J5") (pin "2") (pinfunction "2_2") (pintype "passive"))
      (node (ref "J5") (pin "4") (pinfunction "4_4") (pintype "passive"))
      (node (ref "P2") (pin "4") (pintype "passive"))
      (node (ref "P2") (pin "5") (pintype "passive"))
      (node (ref "R1") (pin "2") (pinfunction "2_2") (pintype "passive"))
      (node (ref "R14") (pin "2") (pinfunction "2_2") (pintype "passive"))
      (node (ref "R2") (pin "1") (pinfunction "1_1") (pintype "passive"))
      (node (ref "R22") (pin "2") (pinfunction "2_2") (pintype "passive"))
      (node (ref "R24") (pin "2") (pinfunction "2_2") (pintype "passive"))
      (node (ref "R28") (pin "1") (pintype "passive"))
      (node (ref "R29") (pin "1") (pintype "passive"))
      (node (ref "R3") (pin "1") (pinfunction "1_1") (pintype "passive"))
      (node (ref "S3") (pin "3") (pinfunction "3_3") (pintype "passive"))
      (node (ref "U2") (pin "11") (pinfunction "VDD_5_11") (pintype "power_in"))
      (node (ref "U2") (pin "28") (pinfunction "VDD_4_28") (pintype "power_in"))
      (node (ref "U2") (pin "75") (pinfunction "VDD_2_75") (pintype "power_in"))
      (node (ref "U3") (pin "14") (pinfunction "VDD33/VIO_14") (pintype "power_in"))
    )
    (net (code "121") (name "5V_in") (class "Default")
      (node (ref "F2") (pin "1") (pinfunction "1_1") (pintype "passive"))
      (node (ref "P6") (pin "A4") (pinfunction "VBUS_A4") (pintype "bidirectional"))
      (node (ref "P6") (pin "B4") (pinfunction "VBUS_B4") (pintype "bidirectional"))
      (node (ref "P7") (pin "A4") (pinfunction "VBUS_A4") (pintype "bidirectional"))
      (node (ref "P7") (pin "B4") (pinfunction "VBUS_B4") (pintype "bidirectional"))
      (node (ref "P9") (pin "A4") (pinfunction "VBUS_A4") (pintype "bidirectional"))
      (node (ref "P9") (pin "B4") (pinfunction "VBUS_B4") (pintype "bidirectional"))
    )
    (net (code "122") (name "GND") (class "Default")
      (node (ref "C1") (pin "1") (pinfunction "1_1") (pintype "passive"))
      (node (ref "C10") (pin "1") (pinfunction "1_1") (pintype "passive"))
      (node (ref "C11") (pin "1") (pinfunction "1_1") (pintype "passive"))
      (node (ref "C12") (pin "2") (pinfunction "2_2") (pintype "passive"))
      (node (ref "C13") (pin "2") (pinfunction "2_2") (pintype "passive"))
      (node (ref "C14") (pin "1") (pinfunction "1_1") (pintype "passive"))
      (node (ref "C2") (pin "1") (pinfunction "1_1") (pintype "passive"))
      (node (ref "C21") (pin "2") (pinfunction "2_2") (pintype "passive"))
      (node (ref "C3") (pin "2") (pinfunction "2_2") (pintype "passive"))
      (node (ref "C31") (pin "1") (pinfunction "1_1") (pintype "passive"))
      (node (ref "C32") (pin "1") (pinfunction "1_1") (pintype "passive"))
      (node (ref "C4") (pin "1") (pinfunction "1_1") (pintype "passive"))
      (node (ref "C46") (pin "2") (pinfunction "2_2") (pintype "passive"))
      (node (ref "C5") (pin "2") (pinfunction "2_2") (pintype "passive"))
      (node (ref "C6") (pin "2") (pinfunction "2_2") (pintype "passive"))
      (node (ref "C7") (pin "1") (pinfunction "1_1") (pintype "passive"))
      (node (ref "C8") (pin "1") (pinfunction "1_1") (pintype "passive"))
      (node (ref "C9") (pin "1") (pinfunction "1_1") (pintype "passive"))
      (node (ref "J2") (pin "5") (pinfunction "5_5") (pintype "passive"))
      (node (ref "J2") (pin "6") (pinfunction "6_6") (pintype "passive"))
      (node (ref "J3") (pin "20") (pinfunction "20_20") (pintype "passive"))
      (node (ref "J3") (pin "22") (pinfunction "22_22") (pintype "passive"))
      (node (ref "J3") (pin "25") (pinfunction "25_25") (pintype "passive"))
      (node (ref "J3") (pin "26") (pinfunction "26_26") (pintype "passive"))
      (node (ref "J3") (pin "7") (pinfunction "7_7") (pintype "passive"))
      (node (ref "J3") (pin "8") (pinfunction "8_8") (pintype "passive"))
      (node (ref "J3") (pin "9") (pinfunction "9_9") (pintype "passive"))
      (node (ref "J4") (pin "7") (pinfunction "7_7") (pintype "passive"))
      (node (ref "J5") (pin "6") (pinfunction "6_6") (pintype "passive"))
      (node (ref "J5") (pin "7") (pinfunction "7_7") (pintype "passive"))
      (node (ref "J7") (pin "4") (pinfunction "4_4") (pintype "passive"))
      (node (ref "P2") (pin "8") (pintype "passive"))
      (node (ref "P6") (pin "A1") (pinfunction "GND_A1") (pintype "bidirectional"))
      (node (ref "P6") (pin "B1") (pinfunction "GND_B1") (pintype "bidirectional"))
      (node (ref "P7") (pin "A1") (pinfunction "GND_A1") (pintype "bidirectional"))
      (node (ref "P7") (pin "B1") (pinfunction "GND_B1") (pintype "bidirectional"))
      (node (ref "P9") (pin "A1") (pinfunction "GND_A1") (pintype "bidirectional"))
      (node (ref "P9") (pin "B1") (pinfunction "GND_B1") (pintype "bidirectional"))
      (node (ref "PWR") (pin "2") (pinfunction "K_2") (pintype "passive"))
      (node (ref "R10") (pin "2") (pinfunction "2_2") (pintype "passive"))
      (node (ref "R11") (pin "2") (pinfunction "2_2") (pintype "passive"))
      (node (ref "R18") (pin "1") (pinfunction "1_1") (pintype "passive"))
      (node (ref "R20") (pin "1") (pinfunction "1_1") (pintype "passive"))
      (node (ref "R21") (pin "1") (pinfunction "1_1") (pintype "passive"))
      (node (ref "R31") (pin "1") (pinfunction "1_1") (pintype "passive"))
      (node (ref "R8") (pin "1") (pinfunction "1_1") (pintype "passive"))
      (node (ref "R9") (pin "1") (pinfunction "1_1") (pintype "passive"))
      (node (ref "S1") (pin "3") (pinfunction "B1_3") (pintype "passive"))
      (node (ref "S2") (pin "3") (pinfunction "B1_3") (pintype "passive"))
      (node (ref "S5") (pin "2") (pinfunction "2_2") (pintype "passive"))
      (node (ref "U1") (pin "1") (pinfunction "GND_1") (pintype "passive"))
      (node (ref "U2") (pin "10") (pinfunction "VSS_5_10") (pintype "power_in"))
      (node (ref "U2") (pin "19") (pinfunction "VSSA_19") (pintype "power_in"))
      (node (ref "U2") (pin "27") (pinfunction "VSS_4_27") (pintype "power_in"))
      (node (ref "U2") (pin "49") (pinfunction "VSS_1_49") (pintype "power_in"))
      (node (ref "U2") (pin "74") (pinfunction "VSS_2_74") (pintype "power_in"))
      (node (ref "U2") (pin "99") (pinfunction "VSS_3_99") (pintype "power_in"))
      (node (ref "U3") (pin "18") (pinfunction "VSS/GND_18") (pintype "power_in"))
    )
    (net (code "123") (name "Net-(D2-K)") (class "Default")
      (node (ref "D2") (pin "2") (pinfunction "K_2") (pintype "passive"))
      (node (ref "R13") (pin "2") (pinfunction "2_2") (pintype "passive"))
    )
    (net (code "124") (name "Net-(D3-K)") (class "Default")
      (node (ref "D3") (pin "2") (pinfunction "K_2") (pintype "passive"))
      (node (ref "R21") (pin "2") (pinfunction "2_2") (pintype "passive"))
    )
    (net (code "125") (name "Net-(J3-Pad6)") (class "Default")
      (node (ref "J3") (pin "6") (pinfunction "6_6") (pintype "passive"))
      (node (ref "R5") (pin "1") (pinfunction "1_1") (pintype "passive"))
    )
    (net (code "126") (name "Net-(J3-Pad10)") (class "Default")
      (node (ref "J3") (pin "10") (pinfunction "10_10") (pintype "passive"))
      (node (ref "J5") (pin "1") (pinfunction "1_1") (pintype "passive"))
    )
    (net (code "127") (name "Net-(LED1-A)") (class "Default")
      (node (ref "LED1") (pin "1") (pinfunction "A_1") (pintype "passive"))
      (node (ref "R2") (pin "2") (pinfunction "2_2") (pintype "passive"))
    )
    (net (code "128") (name "Net-(LED2-A)") (class "Default")
      (node (ref "LED2") (pin "1") (pinfunction "A_1") (pintype "passive"))
      (node (ref "R3") (pin "2") (pinfunction "2_2") (pintype "passive"))
    )
    (net (code "129") (name "Net-(P2-Pad9)") (class "Default")
      (node (ref "P2") (pin "9") (pintype "passive"))
      (node (ref "R28") (pin "2") (pintype "passive"))
    )
    (net (code "130") (name "Net-(P2-Pad12)") (class "Default")
      (node (ref "P2") (pin "12") (pintype "passive"))
      (node (ref "R29") (pin "2") (pintype "passive"))
    )
    (net (code "131") (name "Net-(P6-CC-PadA5)") (class "Default")
      (node (ref "P6") (pin "A5") (pinfunction "CC_A5") (pintype "bidirectional"))
      (node (ref "R20") (pin "2") (pinfunction "2_2") (pintype "passive"))
    )
    (net (code "132") (name "Net-(P6-CC-PadB5)") (class "Default")
      (node (ref "P6") (pin "B5") (pinfunction "CC_B5") (pintype "bidirectional"))
      (node (ref "R31") (pin "2") (pinfunction "2_2") (pintype "passive"))
    )
    (net (code "133") (name "Net-(P7-CC-PadA5)") (class "Default")
      (node (ref "P7") (pin "A5") (pinfunction "CC_A5") (pintype "bidirectional"))
      (node (ref "R8") (pin "2") (pinfunction "2_2") (pintype "passive"))
    )
    (net (code "134") (name "Net-(P7-CC-PadB5)") (class "Default")
      (node (ref "P7") (pin "B5") (pinfunction "CC_B5") (pintype "bidirectional"))
      (node (ref "R9") (pin "2") (pinfunction "2_2") (pintype "passive"))
    )
    (net (code "135") (name "Net-(P9-CC-PadA5)") (class "Default")
      (node (ref "P9") (pin "A5") (pinfunction "CC_A5") (pintype "bidirectional"))
      (node (ref "R10") (pin "1") (pinfunction "1_1") (pintype "passive"))
    )
    (net (code "136") (name "Net-(P9-CC-PadB5)") (class "Default")
      (node (ref "P9") (pin "B5") (pinfunction "CC_B5") (pintype "bidirectional"))
      (node (ref "R11") (pin "1") (pinfunction "1_1") (pintype "passive"))
    )
    (net (code "137") (name "Net-(PWR-A)") (class "Default")
      (node (ref "PWR") (pin "1") (pinfunction "A_1") (pintype "passive"))
      (node (ref "R1") (pin "1") (pinfunction "1_1") (pintype "passive"))
    )
    (net (code "138") (name "Net-(U1-VOUT)") (class "Default")
      (node (ref "C13") (pin "1") (pinfunction "1_1") (pintype "passive"))
      (node (ref "S3") (pin "1") (pinfunction "1_1") (pintype "passive"))
      (node (ref "U1") (pin "2") (pinfunction "VOUT_2") (pintype "passive"))
    )
    (net (code "139") (name "unconnected-(P2-Pad7)") (class "Default")
      (node (ref "P2") (pin "7") (pintype "passive"))
    )
    (net (code "140") (name "unconnected-(P6-RFU1-PadA8)") (class "Default")
      (node (ref "P6") (pin "A8") (pinfunction "RFU1_A8") (pintype "bidirectional+no_connect"))
    )
    (net (code "141") (name "unconnected-(P6-RFU1-PadB8)") (class "Default")
      (node (ref "P6") (pin "B8") (pinfunction "RFU1_B8") (pintype "bidirectional+no_connect"))
    )
    (net (code "142") (name "unconnected-(P7-RFU1-PadA8)") (class "Default")
      (node (ref "P7") (pin "A8") (pinfunction "RFU1_A8") (pintype "bidirectional+no_connect"))
    )
    (net (code "143") (name "unconnected-(P7-RFU1-PadB8)") (class "Default")
      (node (ref "P7") (pin "B8") (pinfunction "RFU1_B8") (pintype "bidirectional+no_connect"))
    )
    (net (code "144") (name "unconnected-(P9-RFU1-PadA8)") (class "Default")
      (node (ref "P9") (pin "A8") (pinfunction "RFU1_A8") (pintype "bidirectional+no_connect"))
    )
    (net (code "145") (name "unconnected-(P9-RFU1-PadB8)") (class "Default")
      (node (ref "P9") (pin "B8") (pinfunction "RFU1_B8") (pintype "bidirectional+no_connect"))
    )
    (net (code "146") (name "unconnected-(S1-A1-Pad4)") (class "Default")
      (node (ref "S1") (pin "4") (pinfunction "A1_4") (pintype "passive"))
    )
    (net (code "147") (name "unconnected-(S1-B0-Pad2)") (class "Default")
      (node (ref "S1") (pin "2") (pinfunction "B0_2") (pintype "passive"))
    )
    (net (code "148") (name "unconnected-(S2-A1-Pad4)") (class "Default")
      (node (ref "S2") (pin "4") (pinfunction "A1_4") (pintype "passive"))
    )
    (net (code "149") (name "unconnected-(S2-B0-Pad2)") (class "Default")
      (node (ref "S2") (pin "2") (pinfunction "B0_2") (pintype "passive"))
    )
    (net (code "150") (name "unconnected-(S3-Pad2)") (class "Default")
      (node (ref "S3") (pin "2") (pinfunction "2_2") (pintype "passive"))
    )
    (net (code "151") (name "unconnected-(U3-PA5{slash}UART1_CTS{slash}PA1_(no5V)-Pad2)") (class "Default")
      (node (ref "U3") (pin "2") (pinfunction "PA5/UART1_CTS/PA1_(no5V)_2") (pintype "bidirectional+no_connect"))
    )
    (net (code "152") (name "unconnected-(U3-PB12{slash}SPI2_NSS{slash}CAN2_RX-Pad5)") (class "Default")
      (node (ref "U3") (pin "5") (pinfunction "PB12/SPI2_NSS/CAN2_RX_5") (pintype "bidirectional+no_connect"))
    )
    (net (code "153") (name "unconnected-(U3-PB14{slash}SPI2_MISO{slash}UART3_RTS-Pad7)") (class "Default")
      (node (ref "U3") (pin "7") (pinfunction "PB14/SPI2_MISO/UART3_RTS_7") (pintype "bidirectional+no_connect"))
    )
    (net (code "154") (name "unconnected-(U3-PB15{slash}SPI2_MOSI{slash}UART1_TX-Pad8)") (class "Default")
      (node (ref "U3") (pin "8") (pinfunction "PB15/SPI2_MOSI/UART1_TX_8") (pintype "bidirectional+no_connect"))
    )
  )
)
